# 20_FPGA_Power.net
KiCad netlist of a schematic drawn in Altium Designer
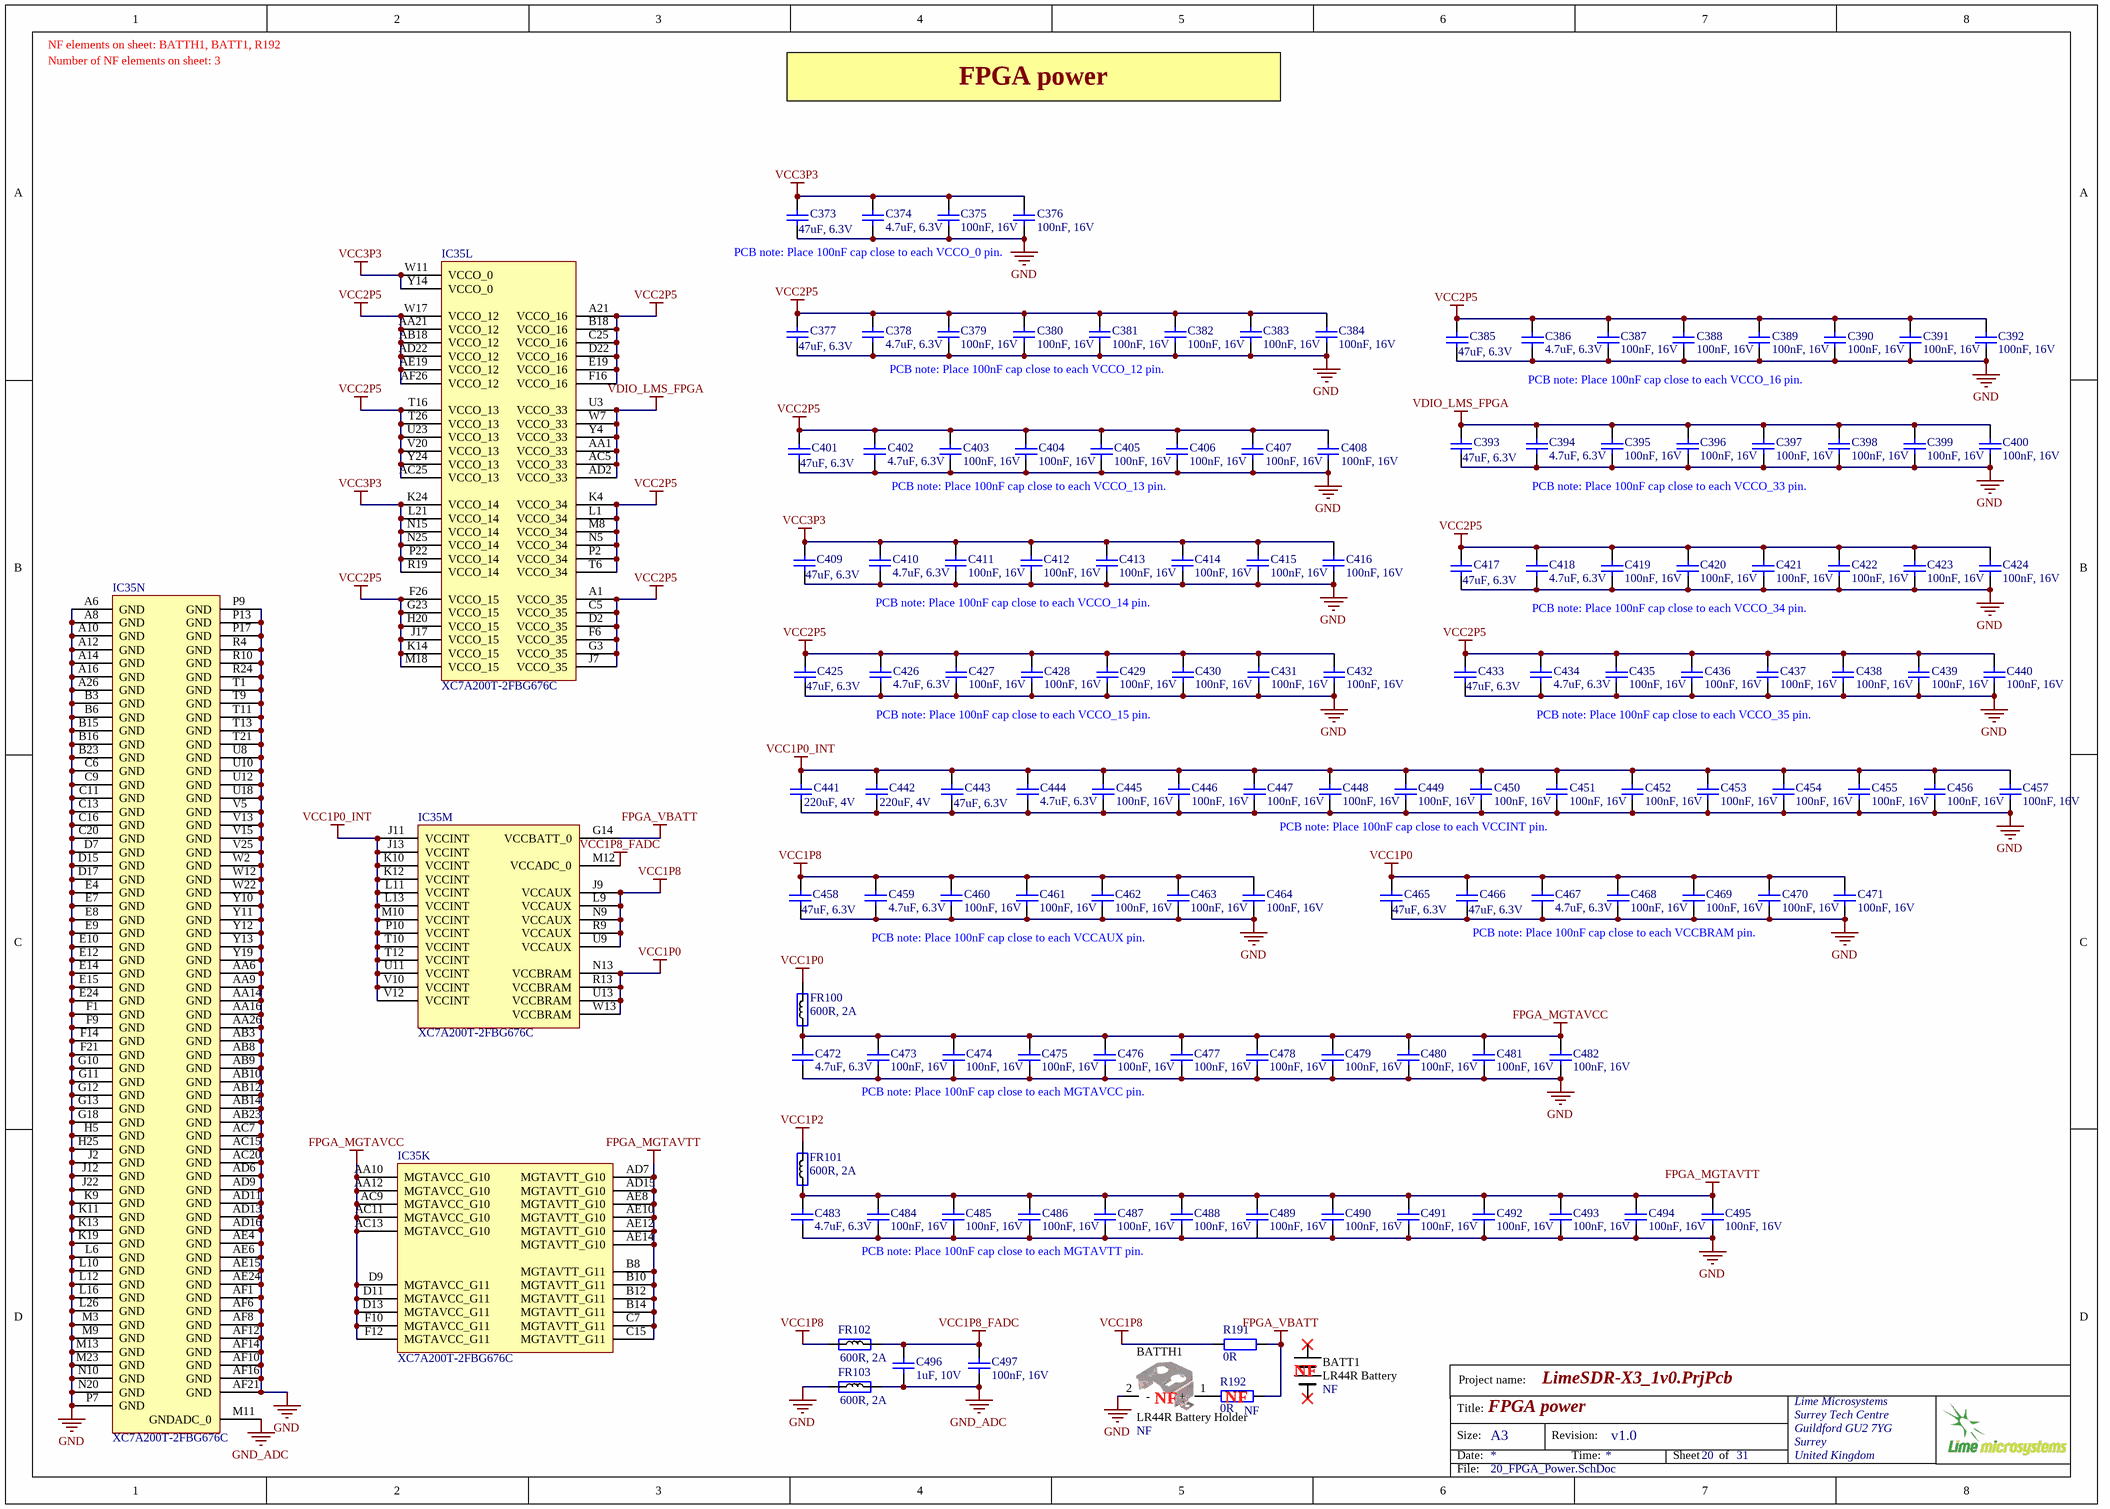
[diagram p0: 20_FPGA_Power.SchDoc]

(export (version "E")
  (design (tool "Eeschema 10.0.6"))
  (components
    (comp (ref "BATT1")
      (value "LR44R Battery")
      (fields (field (name "MANUFACTURER") "Murata") (field (name "ASSEMBLY INFO") "NF"))
      (libsource (lib "LimeMicroAltiumLib_schLib_r03") (part "LR44R_BATTERY"))
    )
    (comp (ref "BATTH1")
      (value "LR44R Battery Holder")
      (footprint "LR44R_BATTERY_HOLDER")
      (fields (field (name "MANUFACTURER") "Keystone Electronics") (field (name "ASSEMBLY INFO") "NF"))
      (libsource (lib "LimeMicroAltiumLib_schLib_r04") (part "LR44R_BATTERY_HOLDER"))
    )
    (comp (ref "C373")
      (value "47uF, 6.3V")
      (footprint "CAP1206")
      (fields
        (field (name "TOLERANCE") "±20%")
        (field (name "MANUFACTURER") "Samsung Electro-Mechanics")
        (field (name "MANUFACTURER PART NUMBER") "CL31A476MQHNNNE")
      )
      (libsource (lib "") (part "Cap_1206_2"))
    )
    (comp (ref "C374")
      (value "4.7uF, 6.3V")
      (footprint "CAP0402")
      (fields
        (field (name "MANUFACTURER") "Murata Electronics North America")
        (field (name "TOLERANCE") "±20%")
      )
      (libsource (lib "LimeMicroAltiumLib_schLib") (part "Cap_0402"))
    )
    (comp (ref "C375")
      (value "100nF, 16V")
      (footprint "CAP0402")
      (fields (field (name "MANUFACTURER") "Murata Electronics") (field (name "TOLERANCE") "10 %"))
      (libsource (lib "LimeMicroAltiumLib_schLib") (part "Cap_0402"))
    )
    (comp (ref "C376")
      (value "100nF, 16V")
      (footprint "CAP0402")
      (fields (field (name "MANUFACTURER") "Murata Electronics") (field (name "TOLERANCE") "10 %"))
      (libsource (lib "LimeMicroAltiumLib_schLib") (part "Cap_0402"))
    )
    (comp (ref "C377")
      (value "47uF, 6.3V")
      (footprint "CAP1206")
      (fields
        (field (name "TOLERANCE") "±20%")
        (field (name "MANUFACTURER") "Samsung Electro-Mechanics")
        (field (name "MANUFACTURER PART NUMBER") "CL31A476MQHNNNE")
      )
      (libsource (lib "") (part "Cap_1206_2"))
    )
    (comp (ref "C378")
      (value "4.7uF, 6.3V")
      (footprint "CAP0402")
      (fields
        (field (name "MANUFACTURER") "Murata Electronics North America")
        (field (name "TOLERANCE") "±20%")
      )
      (libsource (lib "LimeMicroAltiumLib_schLib") (part "Cap_0402"))
    )
    (comp (ref "C379")
      (value "100nF, 16V")
      (footprint "CAP0402")
      (fields (field (name "MANUFACTURER") "Murata Electronics") (field (name "TOLERANCE") "10 %"))
      (libsource (lib "LimeMicroAltiumLib_schLib") (part "Cap_0402"))
    )
    (comp (ref "C380")
      (value "100nF, 16V")
      (footprint "CAP0402")
      (fields (field (name "MANUFACTURER") "Murata Electronics") (field (name "TOLERANCE") "10 %"))
      (libsource (lib "LimeMicroAltiumLib_schLib") (part "Cap_0402"))
    )
    (comp (ref "C381")
      (value "100nF, 16V")
      (footprint "CAP0402")
      (fields (field (name "MANUFACTURER") "Murata Electronics") (field (name "TOLERANCE") "10 %"))
      (libsource (lib "") (part "Cap_0402_1"))
    )
    (comp (ref "C382")
      (value "100nF, 16V")
      (footprint "CAP0402")
      (fields (field (name "MANUFACTURER") "Murata Electronics") (field (name "TOLERANCE") "10 %"))
      (libsource (lib "") (part "Cap_0402_2"))
    )
    (comp (ref "C383")
      (value "100nF, 16V")
      (footprint "CAP0402")
      (fields (field (name "MANUFACTURER") "Murata Electronics") (field (name "TOLERANCE") "10 %"))
      (libsource (lib "") (part "Cap_0402_2"))
    )
    (comp (ref "C384")
      (value "100nF, 16V")
      (footprint "CAP0402")
      (fields (field (name "MANUFACTURER") "Murata Electronics") (field (name "TOLERANCE") "10 %"))
      (libsource (lib "LimeMicroAltiumLib_schLib") (part "Cap_0402"))
    )
    (comp (ref "C385")
      (value "47uF, 6.3V")
      (footprint "CAP1206")
      (fields
        (field (name "TOLERANCE") "±20%")
        (field (name "MANUFACTURER") "Samsung Electro-Mechanics")
        (field (name "MANUFACTURER PART NUMBER") "CL31A476MQHNNNE")
      )
      (libsource (lib "") (part "Cap_1206_2"))
    )
    (comp (ref "C386")
      (value "4.7uF, 6.3V")
      (footprint "CAP0402")
      (fields
        (field (name "MANUFACTURER") "Murata Electronics North America")
        (field (name "TOLERANCE") "±20%")
      )
      (libsource (lib "LimeMicroAltiumLib_schLib") (part "Cap_0402"))
    )
    (comp (ref "C387")
      (value "100nF, 16V")
      (footprint "CAP0402")
      (fields (field (name "MANUFACTURER") "Murata Electronics") (field (name "TOLERANCE") "10 %"))
      (libsource (lib "LimeMicroAltiumLib_schLib") (part "Cap_0402"))
    )
    (comp (ref "C388")
      (value "100nF, 16V")
      (footprint "CAP0402")
      (fields (field (name "MANUFACTURER") "Murata Electronics") (field (name "TOLERANCE") "10 %"))
      (libsource (lib "LimeMicroAltiumLib_schLib") (part "Cap_0402"))
    )
    (comp (ref "C389")
      (value "100nF, 16V")
      (footprint "CAP0402")
      (fields (field (name "MANUFACTURER") "Murata Electronics") (field (name "TOLERANCE") "10 %"))
      (libsource (lib "") (part "Cap_0402_1"))
    )
    (comp (ref "C390")
      (value "100nF, 16V")
      (footprint "CAP0402")
      (fields (field (name "MANUFACTURER") "Murata Electronics") (field (name "TOLERANCE") "10 %"))
      (libsource (lib "") (part "Cap_0402_2"))
    )
    (comp (ref "C391")
      (value "100nF, 16V")
      (footprint "CAP0402")
      (fields (field (name "MANUFACTURER") "Murata Electronics") (field (name "TOLERANCE") "10 %"))
      (libsource (lib "") (part "Cap_0402_2"))
    )
    (comp (ref "C392")
      (value "100nF, 16V")
      (footprint "CAP0402")
      (fields (field (name "MANUFACTURER") "Murata Electronics") (field (name "TOLERANCE") "10 %"))
      (libsource (lib "LimeMicroAltiumLib_schLib") (part "Cap_0402"))
    )
    (comp (ref "C393")
      (value "47uF, 6.3V")
      (footprint "CAP1206")
      (fields
        (field (name "TOLERANCE") "±20%")
        (field (name "MANUFACTURER") "Samsung Electro-Mechanics")
        (field (name "MANUFACTURER PART NUMBER") "CL31A476MQHNNNE")
      )
      (libsource (lib "LimeFPGAboard_schLib") (part "Cap_1206"))
    )
    (comp (ref "C394")
      (value "4.7uF, 6.3V")
      (footprint "CAP0402")
      (fields
        (field (name "MANUFACTURER") "Murata Electronics North America")
        (field (name "TOLERANCE") "±20%")
      )
      (libsource (lib "LimeMicroAltiumLib_schLib") (part "Cap_0402"))
    )
    (comp (ref "C395")
      (value "100nF, 16V")
      (footprint "CAP0402")
      (fields (field (name "MANUFACTURER") "Murata Electronics") (field (name "TOLERANCE") "10 %"))
      (libsource (lib "") (part "Cap_0402_2"))
    )
    (comp (ref "C396")
      (value "100nF, 16V")
      (footprint "CAP0402")
      (fields (field (name "MANUFACTURER") "Murata Electronics") (field (name "TOLERANCE") "10 %"))
      (libsource (lib "LimeMicroAltiumLib_schLib") (part "Cap_0402"))
    )
    (comp (ref "C397")
      (value "100nF, 16V")
      (footprint "CAP0402")
      (fields (field (name "MANUFACTURER") "Murata Electronics") (field (name "TOLERANCE") "10 %"))
      (libsource (lib "LimeMicroAltiumLib_schLib") (part "Cap_0402"))
    )
    (comp (ref "C398")
      (value "100nF, 16V")
      (footprint "CAP0402")
      (fields (field (name "MANUFACTURER") "Murata Electronics") (field (name "TOLERANCE") "10 %"))
      (libsource (lib "") (part "Cap_0402_1"))
    )
    (comp (ref "C399")
      (value "100nF, 16V")
      (footprint "CAP0402")
      (fields (field (name "MANUFACTURER") "Murata Electronics") (field (name "TOLERANCE") "10 %"))
      (libsource (lib "") (part "Cap_0402_2"))
    )
    (comp (ref "C400")
      (value "100nF, 16V")
      (footprint "CAP0402")
      (fields (field (name "MANUFACTURER") "Murata Electronics") (field (name "TOLERANCE") "10 %"))
      (libsource (lib "") (part "Cap_0402_2"))
    )
    (comp (ref "C401")
      (value "47uF, 6.3V")
      (footprint "CAP1206")
      (fields
        (field (name "TOLERANCE") "±20%")
        (field (name "MANUFACTURER") "Samsung Electro-Mechanics")
        (field (name "MANUFACTURER PART NUMBER") "CL31A476MQHNNNE")
      )
      (libsource (lib "") (part "Cap_1206_1"))
    )
    (comp (ref "C402")
      (value "4.7uF, 6.3V")
      (footprint "CAP0402")
      (fields
        (field (name "MANUFACTURER") "Murata Electronics North America")
        (field (name "TOLERANCE") "±20%")
      )
      (libsource (lib "") (part "Cap_0402_2"))
    )
    (comp (ref "C403")
      (value "100nF, 16V")
      (footprint "CAP0402")
      (fields (field (name "MANUFACTURER") "Murata Electronics") (field (name "TOLERANCE") "10 %"))
      (libsource (lib "") (part "Cap_0402_1"))
    )
    (comp (ref "C404")
      (value "100nF, 16V")
      (footprint "CAP0402")
      (fields (field (name "MANUFACTURER") "Murata Electronics") (field (name "TOLERANCE") "10 %"))
      (libsource (lib "") (part "Cap_0402_2"))
    )
    (comp (ref "C405")
      (value "100nF, 16V")
      (footprint "CAP0402")
      (fields (field (name "MANUFACTURER") "Murata Electronics") (field (name "TOLERANCE") "10 %"))
      (libsource (lib "") (part "Cap_0402_2"))
    )
    (comp (ref "C406")
      (value "100nF, 16V")
      (footprint "CAP0402")
      (fields (field (name "MANUFACTURER") "Murata Electronics") (field (name "TOLERANCE") "10 %"))
      (libsource (lib "LimeMicroAltiumLib_schLib") (part "Cap_0402"))
    )
    (comp (ref "C407")
      (value "100nF, 16V")
      (footprint "CAP0402")
      (fields (field (name "MANUFACTURER") "Murata Electronics") (field (name "TOLERANCE") "10 %"))
      (libsource (lib "LimeMicroAltiumLib_schLib") (part "Cap_0402"))
    )
    (comp (ref "C408")
      (value "100nF, 16V")
      (footprint "CAP0402")
      (fields (field (name "MANUFACTURER") "Murata Electronics") (field (name "TOLERANCE") "10 %"))
      (libsource (lib "") (part "Cap_0402_1"))
    )
    (comp (ref "C409")
      (value "47uF, 6.3V")
      (footprint "CAP1206")
      (fields
        (field (name "TOLERANCE") "±20%")
        (field (name "MANUFACTURER") "Samsung Electro-Mechanics")
        (field (name "MANUFACTURER PART NUMBER") "CL31A476MQHNNNE")
      )
      (libsource (lib "") (part "Cap_1206_1"))
    )
    (comp (ref "C410")
      (value "4.7uF, 6.3V")
      (footprint "CAP0402")
      (fields
        (field (name "MANUFACTURER") "Murata Electronics North America")
        (field (name "TOLERANCE") "±20%")
      )
      (libsource (lib "") (part "Cap_0402_2"))
    )
    (comp (ref "C411")
      (value "100nF, 16V")
      (footprint "CAP0402")
      (fields (field (name "MANUFACTURER") "Murata Electronics") (field (name "TOLERANCE") "10 %"))
      (libsource (lib "") (part "Cap_0402_1"))
    )
    (comp (ref "C412")
      (value "100nF, 16V")
      (footprint "CAP0402")
      (fields (field (name "MANUFACTURER") "Murata Electronics") (field (name "TOLERANCE") "10 %"))
      (libsource (lib "") (part "Cap_0402_2"))
    )
    (comp (ref "C413")
      (value "100nF, 16V")
      (footprint "CAP0402")
      (fields (field (name "MANUFACTURER") "Murata Electronics") (field (name "TOLERANCE") "10 %"))
      (libsource (lib "") (part "Cap_0402_2"))
    )
    (comp (ref "C414")
      (value "100nF, 16V")
      (footprint "CAP0402")
      (fields (field (name "MANUFACTURER") "Murata Electronics") (field (name "TOLERANCE") "10 %"))
      (libsource (lib "LimeMicroAltiumLib_schLib") (part "Cap_0402"))
    )
    (comp (ref "C415")
      (value "100nF, 16V")
      (footprint "CAP0402")
      (fields (field (name "MANUFACTURER") "Murata Electronics") (field (name "TOLERANCE") "10 %"))
      (libsource (lib "LimeMicroAltiumLib_schLib") (part "Cap_0402"))
    )
    (comp (ref "C416")
      (value "100nF, 16V")
      (footprint "CAP0402")
      (fields (field (name "MANUFACTURER") "Murata Electronics") (field (name "TOLERANCE") "10 %"))
      (libsource (lib "") (part "Cap_0402_1"))
    )
    (comp (ref "C417")
      (value "47uF, 6.3V")
      (footprint "CAP1206")
      (fields
        (field (name "TOLERANCE") "±20%")
        (field (name "MANUFACTURER") "Samsung Electro-Mechanics")
        (field (name "MANUFACTURER PART NUMBER") "CL31A476MQHNNNE")
      )
      (libsource (lib "LimeFPGAboard_schLib") (part "Cap_1206"))
    )
    (comp (ref "C418")
      (value "4.7uF, 6.3V")
      (footprint "CAP0402")
      (fields
        (field (name "MANUFACTURER") "Murata Electronics North America")
        (field (name "TOLERANCE") "±20%")
      )
      (libsource (lib "LimeMicroAltiumLib_schLib") (part "Cap_0402"))
    )
    (comp (ref "C419")
      (value "100nF, 16V")
      (footprint "CAP0402")
      (fields (field (name "MANUFACTURER") "Murata Electronics") (field (name "TOLERANCE") "10 %"))
      (libsource (lib "") (part "Cap_0402_2"))
    )
    (comp (ref "C420")
      (value "100nF, 16V")
      (footprint "CAP0402")
      (fields (field (name "MANUFACTURER") "Murata Electronics") (field (name "TOLERANCE") "10 %"))
      (libsource (lib "LimeMicroAltiumLib_schLib") (part "Cap_0402"))
    )
    (comp (ref "C421")
      (value "100nF, 16V")
      (footprint "CAP0402")
      (fields (field (name "MANUFACTURER") "Murata Electronics") (field (name "TOLERANCE") "10 %"))
      (libsource (lib "LimeMicroAltiumLib_schLib") (part "Cap_0402"))
    )
    (comp (ref "C422")
      (value "100nF, 16V")
      (footprint "CAP0402")
      (fields (field (name "MANUFACTURER") "Murata Electronics") (field (name "TOLERANCE") "10 %"))
      (libsource (lib "") (part "Cap_0402_1"))
    )
    (comp (ref "C423")
      (value "100nF, 16V")
      (footprint "CAP0402")
      (fields (field (name "MANUFACTURER") "Murata Electronics") (field (name "TOLERANCE") "10 %"))
      (libsource (lib "") (part "Cap_0402_2"))
    )
    (comp (ref "C424")
      (value "100nF, 16V")
      (footprint "CAP0402")
      (fields (field (name "MANUFACTURER") "Murata Electronics") (field (name "TOLERANCE") "10 %"))
      (libsource (lib "") (part "Cap_0402_2"))
    )
    (comp (ref "C425")
      (value "47uF, 6.3V")
      (footprint "CAP1206")
      (fields
        (field (name "TOLERANCE") "±20%")
        (field (name "MANUFACTURER") "Samsung Electro-Mechanics")
        (field (name "MANUFACTURER PART NUMBER") "CL31A476MQHNNNE")
      )
      (libsource (lib "") (part "Cap_1206_1"))
    )
    (comp (ref "C426")
      (value "4.7uF, 6.3V")
      (footprint "CAP0402")
      (fields
        (field (name "MANUFACTURER") "Murata Electronics North America")
        (field (name "TOLERANCE") "±20%")
      )
      (libsource (lib "") (part "Cap_0402_2"))
    )
    (comp (ref "C427")
      (value "100nF, 16V")
      (footprint "CAP0402")
      (fields (field (name "MANUFACTURER") "Murata Electronics") (field (name "TOLERANCE") "10 %"))
      (libsource (lib "") (part "Cap_0402_1"))
    )
    (comp (ref "C428")
      (value "100nF, 16V")
      (footprint "CAP0402")
      (fields (field (name "MANUFACTURER") "Murata Electronics") (field (name "TOLERANCE") "10 %"))
      (libsource (lib "") (part "Cap_0402_2"))
    )
    (comp (ref "C429")
      (value "100nF, 16V")
      (footprint "CAP0402")
      (fields (field (name "MANUFACTURER") "Murata Electronics") (field (name "TOLERANCE") "10 %"))
      (libsource (lib "") (part "Cap_0402_2"))
    )
    (comp (ref "C430")
      (value "100nF, 16V")
      (footprint "CAP0402")
      (fields (field (name "MANUFACTURER") "Murata Electronics") (field (name "TOLERANCE") "10 %"))
      (libsource (lib "LimeMicroAltiumLib_schLib") (part "Cap_0402"))
    )
    (comp (ref "C431")
      (value "100nF, 16V")
      (footprint "CAP0402")
      (fields (field (name "MANUFACTURER") "Murata Electronics") (field (name "TOLERANCE") "10 %"))
      (libsource (lib "LimeMicroAltiumLib_schLib") (part "Cap_0402"))
    )
    (comp (ref "C432")
      (value "100nF, 16V")
      (footprint "CAP0402")
      (fields (field (name "MANUFACTURER") "Murata Electronics") (field (name "TOLERANCE") "10 %"))
      (libsource (lib "") (part "Cap_0402_1"))
    )
    (comp (ref "C433")
      (value "47uF, 6.3V")
      (footprint "CAP1206")
      (fields
        (field (name "TOLERANCE") "±20%")
        (field (name "MANUFACTURER") "Samsung Electro-Mechanics")
        (field (name "MANUFACTURER PART NUMBER") "CL31A476MQHNNNE")
      )
      (libsource (lib "") (part "Cap_1206_1"))
    )
    (comp (ref "C434")
      (value "4.7uF, 6.3V")
      (footprint "CAP0402")
      (fields
        (field (name "MANUFACTURER") "Murata Electronics North America")
        (field (name "TOLERANCE") "±20%")
      )
      (libsource (lib "") (part "Cap_0402_1"))
    )
    (comp (ref "C435")
      (value "100nF, 16V")
      (footprint "CAP0402")
      (fields (field (name "MANUFACTURER") "Murata Electronics") (field (name "TOLERANCE") "10 %"))
      (libsource (lib "") (part "Cap_0402_2"))
    )
    (comp (ref "C436")
      (value "100nF, 16V")
      (footprint "CAP0402")
      (fields (field (name "MANUFACTURER") "Murata Electronics") (field (name "TOLERANCE") "10 %"))
      (libsource (lib "") (part "Cap_0402_2"))
    )
    (comp (ref "C437")
      (value "100nF, 16V")
      (footprint "CAP0402")
      (fields (field (name "MANUFACTURER") "Murata Electronics") (field (name "TOLERANCE") "10 %"))
      (libsource (lib "LimeMicroAltiumLib_schLib") (part "Cap_0402"))
    )
    (comp (ref "C438")
      (value "100nF, 16V")
      (footprint "CAP0402")
      (fields (field (name "MANUFACTURER") "Murata Electronics") (field (name "TOLERANCE") "10 %"))
      (libsource (lib "LimeMicroAltiumLib_schLib") (part "Cap_0402"))
    )
    (comp (ref "C439")
      (value "100nF, 16V")
      (footprint "CAP0402")
      (fields (field (name "MANUFACTURER") "Murata Electronics") (field (name "TOLERANCE") "10 %"))
      (libsource (lib "") (part "Cap_0402_1"))
    )
    (comp (ref "C440")
      (value "100nF, 16V")
      (footprint "CAP0402")
      (fields (field (name "MANUFACTURER") "Murata Electronics") (field (name "TOLERANCE") "10 %"))
      (libsource (lib "") (part "Cap_0402_2"))
    )
    (comp (ref "C441")
      (value "220uF, 4V")
      (footprint "CAP1206")
      (fields
        (field (name "MANUFACTURER") "Murata Electronics North America")
        (field (name "TOLERANCE") "±20%")
      )
      (libsource (lib "LimeFPGAboard_schLib") (part "Cap_1206"))
    )
    (comp (ref "C442")
      (value "220uF, 4V")
      (footprint "CAP1206")
      (fields
        (field (name "MANUFACTURER") "Murata Electronics North America")
        (field (name "TOLERANCE") "±20%")
      )
      (libsource (lib "") (part "Cap_1206_2"))
    )
    (comp (ref "C443")
      (value "47uF, 6.3V")
      (footprint "CAP1206")
      (fields
        (field (name "TOLERANCE") "±20%")
        (field (name "MANUFACTURER") "Samsung Electro-Mechanics")
        (field (name "MANUFACTURER PART NUMBER") "CL31A476MQHNNNE")
      )
      (libsource (lib "") (part "Cap_1206_2"))
    )
    (comp (ref "C444")
      (value "4.7uF, 6.3V")
      (footprint "CAP0402")
      (fields
        (field (name "MANUFACTURER") "Murata Electronics North America")
        (field (name "TOLERANCE") "±20%")
      )
      (libsource (lib "") (part "Cap_0402_2"))
    )
    (comp (ref "C445")
      (value "100nF, 16V")
      (footprint "CAP0402")
      (fields (field (name "MANUFACTURER") "Murata Electronics") (field (name "TOLERANCE") "10 %"))
      (libsource (lib "LimeMicroAltiumLib_schLib") (part "Cap_0402"))
    )
    (comp (ref "C446")
      (value "100nF, 16V")
      (footprint "CAP0402")
      (fields (field (name "MANUFACTURER") "Murata Electronics") (field (name "TOLERANCE") "10 %"))
      (libsource (lib "") (part "Cap_0402_1"))
    )
    (comp (ref "C447")
      (value "100nF, 16V")
      (footprint "CAP0402")
      (fields (field (name "MANUFACTURER") "Murata Electronics") (field (name "TOLERANCE") "10 %"))
      (libsource (lib "") (part "Cap_0402_2"))
    )
    (comp (ref "C448")
      (value "100nF, 16V")
      (footprint "CAP0402")
      (fields (field (name "MANUFACTURER") "Murata Electronics") (field (name "TOLERANCE") "10 %"))
      (libsource (lib "") (part "Cap_0402_2"))
    )
    (comp (ref "C449")
      (value "100nF, 16V")
      (footprint "CAP0402")
      (fields (field (name "MANUFACTURER") "Murata Electronics") (field (name "TOLERANCE") "10 %"))
      (libsource (lib "LimeMicroAltiumLib_schLib") (part "Cap_0402"))
    )
    (comp (ref "C450")
      (value "100nF, 16V")
      (footprint "CAP0402")
      (fields (field (name "MANUFACTURER") "Murata Electronics") (field (name "TOLERANCE") "10 %"))
      (libsource (lib "LimeMicroAltiumLib_schLib") (part "Cap_0402"))
    )
    (comp (ref "C451")
      (value "100nF, 16V")
      (footprint "CAP0402")
      (fields (field (name "MANUFACTURER") "Murata Electronics") (field (name "TOLERANCE") "10 %"))
      (libsource (lib "") (part "Cap_0402_1"))
    )
    (comp (ref "C452")
      (value "100nF, 16V")
      (footprint "CAP0402")
      (fields (field (name "MANUFACTURER") "Murata Electronics") (field (name "TOLERANCE") "10 %"))
      (libsource (lib "") (part "Cap_0402_2"))
    )
    (comp (ref "C453")
      (value "100nF, 16V")
      (footprint "CAP0402")
      (fields (field (name "MANUFACTURER") "Murata Electronics") (field (name "TOLERANCE") "10 %"))
      (libsource (lib "") (part "Cap_0402_2"))
    )
    (comp (ref "C454")
      (value "100nF, 16V")
      (footprint "CAP0402")
      (fields (field (name "MANUFACTURER") "Murata Electronics") (field (name "TOLERANCE") "10 %"))
      (libsource (lib "LimeMicroAltiumLib_schLib") (part "Cap_0402"))
    )
    (comp (ref "C455")
      (value "100nF, 16V")
      (footprint "CAP0402")
      (fields (field (name "MANUFACTURER") "Murata Electronics") (field (name "TOLERANCE") "10 %"))
      (libsource (lib "LimeMicroAltiumLib_schLib") (part "Cap_0402"))
    )
    (comp (ref "C456")
      (value "100nF, 16V")
      (footprint "CAP0402")
      (fields (field (name "MANUFACTURER") "Murata Electronics") (field (name "TOLERANCE") "10 %"))
      (libsource (lib "") (part "Cap_0402_1"))
    )
    (comp (ref "C457")
      (value "100nF, 16V")
      (footprint "CAP0402")
      (fields (field (name "MANUFACTURER") "Murata Electronics") (field (name "TOLERANCE") "10 %"))
      (libsource (lib "") (part "Cap_0402_2"))
    )
    (comp (ref "C458")
      (value "47uF, 6.3V")
      (footprint "CAP1206")
      (fields
        (field (name "TOLERANCE") "±20%")
        (field (name "MANUFACTURER") "Samsung Electro-Mechanics")
        (field (name "MANUFACTURER PART NUMBER") "CL31A476MQHNNNE")
      )
      (libsource (lib "") (part "Cap_1206_1"))
    )
    (comp (ref "C459")
      (value "4.7uF, 6.3V")
      (footprint "CAP0402")
      (fields
        (field (name "MANUFACTURER") "Murata Electronics North America")
        (field (name "TOLERANCE") "±20%")
      )
      (libsource (lib "") (part "Cap_0402_2"))
    )
    (comp (ref "C460")
      (value "100nF, 16V")
      (footprint "CAP0402")
      (fields (field (name "MANUFACTURER") "Murata Electronics") (field (name "TOLERANCE") "10 %"))
      (libsource (lib "") (part "Cap_0402_1"))
    )
    (comp (ref "C461")
      (value "100nF, 16V")
      (footprint "CAP0402")
      (fields (field (name "MANUFACTURER") "Murata Electronics") (field (name "TOLERANCE") "10 %"))
      (libsource (lib "") (part "Cap_0402_2"))
    )
    (comp (ref "C462")
      (value "100nF, 16V")
      (footprint "CAP0402")
      (fields (field (name "MANUFACTURER") "Murata Electronics") (field (name "TOLERANCE") "10 %"))
      (libsource (lib "") (part "Cap_0402_2"))
    )
    (comp (ref "C463")
      (value "100nF, 16V")
      (footprint "CAP0402")
      (fields (field (name "MANUFACTURER") "Murata Electronics") (field (name "TOLERANCE") "10 %"))
      (libsource (lib "LimeMicroAltiumLib_schLib") (part "Cap_0402"))
    )
    (comp (ref "C464")
      (value "100nF, 16V")
      (footprint "CAP0402")
      (fields (field (name "MANUFACTURER") "Murata Electronics") (field (name "TOLERANCE") "10 %"))
      (libsource (lib "LimeMicroAltiumLib_schLib") (part "Cap_0402"))
    )
    (comp (ref "C465")
      (value "47uF, 6.3V")
      (footprint "CAP1206")
      (fields
        (field (name "TOLERANCE") "±20%")
        (field (name "MANUFACTURER") "Samsung Electro-Mechanics")
        (field (name "MANUFACTURER PART NUMBER") "CL31A476MQHNNNE")
      )
      (libsource (lib "") (part "Cap_1206_1"))
    )
    (comp (ref "C466")
      (value "47uF, 6.3V")
      (footprint "CAP1206")
      (fields
        (field (name "TOLERANCE") "±20%")
        (field (name "MANUFACTURER") "Samsung Electro-Mechanics")
        (field (name "MANUFACTURER PART NUMBER") "CL31A476MQHNNNE")
      )
      (libsource (lib "LimeFPGAboard_schLib") (part "Cap_1206"))
    )
    (comp (ref "C467")
      (value "4.7uF, 6.3V")
      (footprint "CAP0402")
      (fields
        (field (name "MANUFACTURER") "Murata Electronics North America")
        (field (name "TOLERANCE") "±20%")
      )
      (libsource (lib "LimeMicroAltiumLib_schLib") (part "Cap_0402"))
    )
    (comp (ref "C468")
      (value "100nF, 16V")
      (footprint "CAP0402")
      (fields (field (name "MANUFACTURER") "Murata Electronics") (field (name "TOLERANCE") "10 %"))
      (libsource (lib "") (part "Cap_0402_2"))
    )
    (comp (ref "C469")
      (value "100nF, 16V")
      (footprint "CAP0402")
      (fields (field (name "MANUFACTURER") "Murata Electronics") (field (name "TOLERANCE") "10 %"))
      (libsource (lib "LimeMicroAltiumLib_schLib") (part "Cap_0402"))
    )
    (comp (ref "C470")
      (value "100nF, 16V")
      (footprint "CAP0402")
      (fields (field (name "MANUFACTURER") "Murata Electronics") (field (name "TOLERANCE") "10 %"))
      (libsource (lib "LimeMicroAltiumLib_schLib") (part "Cap_0402"))
    )
    (comp (ref "C471")
      (value "100nF, 16V")
      (footprint "CAP0402")
      (fields (field (name "MANUFACTURER") "Murata Electronics") (field (name "TOLERANCE") "10 %"))
      (libsource (lib "LimeMicroAltiumLib_schLib") (part "Cap_0402"))
    )
    (comp (ref "C472")
      (value "4.7uF, 6.3V")
      (footprint "CAP0402")
      (fields
        (field (name "MANUFACTURER") "Murata Electronics North America")
        (field (name "TOLERANCE") "±20%")
      )
      (libsource (lib "") (part "Cap_0402_1"))
    )
    (comp (ref "C473")
      (value "100nF, 16V")
      (footprint "CAP0402")
      (fields (field (name "MANUFACTURER") "Murata Electronics") (field (name "TOLERANCE") "10 %"))
      (libsource (lib "") (part "Cap_0402_2"))
    )
    (comp (ref "C474")
      (value "100nF, 16V")
      (footprint "CAP0402")
      (fields (field (name "MANUFACTURER") "Murata Electronics") (field (name "TOLERANCE") "10 %"))
      (libsource (lib "") (part "Cap_0402_2"))
    )
    (comp (ref "C475")
      (value "100nF, 16V")
      (footprint "CAP0402")
      (fields (field (name "MANUFACTURER") "Murata Electronics") (field (name "TOLERANCE") "10 %"))
      (libsource (lib "LimeMicroAltiumLib_schLib") (part "Cap_0402"))
    )
    (comp (ref "C476")
      (value "100nF, 16V")
      (footprint "CAP0402")
      (fields (field (name "MANUFACTURER") "Murata Electronics") (field (name "TOLERANCE") "10 %"))
      (libsource (lib "LimeMicroAltiumLib_schLib") (part "Cap_0402"))
    )
    (comp (ref "C477")
      (value "100nF, 16V")
      (footprint "CAP0402")
      (fields (field (name "MANUFACTURER") "Murata Electronics") (field (name "TOLERANCE") "10 %"))
      (libsource (lib "") (part "Cap_0402_3"))
    )
    (comp (ref "C478")
      (value "100nF, 16V")
      (footprint "CAP0402")
      (fields (field (name "MANUFACTURER") "Murata Electronics") (field (name "TOLERANCE") "10 %"))
      (libsource (lib "") (part "Cap_0402_2"))
    )
    (comp (ref "C479")
      (value "100nF, 16V")
      (footprint "CAP0402")
      (fields (field (name "MANUFACTURER") "Murata Electronics") (field (name "TOLERANCE") "10 %"))
      (libsource (lib "") (part "Cap_0402_2"))
    )
    (comp (ref "C480")
      (value "100nF, 16V")
      (footprint "CAP0402")
      (fields (field (name "MANUFACTURER") "Murata Electronics") (field (name "TOLERANCE") "10 %"))
      (libsource (lib "LimeMicroAltiumLib_schLib") (part "Cap_0402"))
    )
    (comp (ref "C481")
      (value "100nF, 16V")
      (footprint "CAP0402")
      (fields (field (name "MANUFACTURER") "Murata Electronics") (field (name "TOLERANCE") "10 %"))
      (libsource (lib "LimeMicroAltiumLib_schLib") (part "Cap_0402"))
    )
    (comp (ref "C482")
      (value "100nF, 16V")
      (footprint "CAP0402")
      (fields (field (name "MANUFACTURER") "Murata Electronics") (field (name "TOLERANCE") "10 %"))
      (libsource (lib "") (part "Cap_0402_3"))
    )
    (comp (ref "C483")
      (value "4.7uF, 6.3V")
      (footprint "CAP0402")
      (fields
        (field (name "MANUFACTURER") "Murata Electronics North America")
        (field (name "TOLERANCE") "±20%")
      )
      (libsource (lib "") (part "Cap_0402_2"))
    )
    (comp (ref "C484")
      (value "100nF, 16V")
      (footprint "CAP0402")
      (fields (field (name "MANUFACTURER") "Murata Electronics") (field (name "TOLERANCE") "10 %"))
      (libsource (lib "") (part "Cap_0402_2"))
    )
    (comp (ref "C485")
      (value "100nF, 16V")
      (footprint "CAP0402")
      (fields (field (name "MANUFACTURER") "Murata Electronics") (field (name "TOLERANCE") "10 %"))
      (libsource (lib "LimeMicroAltiumLib_schLib") (part "Cap_0402"))
    )
    (comp (ref "C486")
      (value "100nF, 16V")
      (footprint "CAP0402")
      (fields (field (name "MANUFACTURER") "Murata Electronics") (field (name "TOLERANCE") "10 %"))
      (libsource (lib "LimeMicroAltiumLib_schLib") (part "Cap_0402"))
    )
    (comp (ref "C487")
      (value "100nF, 16V")
      (footprint "CAP0402")
      (fields (field (name "MANUFACTURER") "Murata Electronics") (field (name "TOLERANCE") "10 %"))
      (libsource (lib "") (part "Cap_0402_1"))
    )
    (comp (ref "C488")
      (value "100nF, 16V")
      (footprint "CAP0402")
      (fields (field (name "MANUFACTURER") "Murata Electronics") (field (name "TOLERANCE") "10 %"))
      (libsource (lib "") (part "Cap_0402_2"))
    )
    (comp (ref "C489")
      (value "100nF, 16V")
      (footprint "CAP0402")
      (fields (field (name "MANUFACTURER") "Murata Electronics") (field (name "TOLERANCE") "10 %"))
      (libsource (lib "") (part "Cap_0402_2"))
    )
    (comp (ref "C490")
      (value "100nF, 16V")
      (footprint "CAP0402")
      (fields (field (name "MANUFACTURER") "Murata Electronics") (field (name "TOLERANCE") "10 %"))
      (libsource (lib "") (part "Cap_0402_2"))
    )
    (comp (ref "C491")
      (value "100nF, 16V")
      (footprint "CAP0402")
      (fields (field (name "MANUFACTURER") "Murata Electronics") (field (name "TOLERANCE") "10 %"))
      (libsource (lib "LimeMicroAltiumLib_schLib") (part "Cap_0402"))
    )
    (comp (ref "C492")
      (value "100nF, 16V")
      (footprint "CAP0402")
      (fields (field (name "MANUFACTURER") "Murata Electronics") (field (name "TOLERANCE") "10 %"))
      (libsource (lib "LimeMicroAltiumLib_schLib") (part "Cap_0402"))
    )
    (comp (ref "C493")
      (value "100nF, 16V")
      (footprint "CAP0402")
      (fields (field (name "MANUFACTURER") "Murata Electronics") (field (name "TOLERANCE") "10 %"))
      (libsource (lib "") (part "Cap_0402_3"))
    )
    (comp (ref "C494")
      (value "100nF, 16V")
      (footprint "CAP0402")
      (fields (field (name "MANUFACTURER") "Murata Electronics") (field (name "TOLERANCE") "10 %"))
      (libsource (lib "LimeMicroAltiumLib_schLib") (part "Cap_0402"))
    )
    (comp (ref "C495")
      (value "100nF, 16V")
      (footprint "CAP0402")
      (fields (field (name "MANUFACTURER") "Murata Electronics") (field (name "TOLERANCE") "10 %"))
      (libsource (lib "") (part "Cap_0402_3"))
    )
    (comp (ref "C496")
      (value "1uF, 10V")
      (footprint "CAP0402")
      (fields (field (name "MANUFACTURER") "TDK"))
      (libsource (lib "") (part "Cap_0402_1"))
    )
    (comp (ref "C497")
      (value "100nF, 16V")
      (footprint "CAP0402")
      (fields (field (name "MANUFACTURER") "Murata Electronics") (field (name "TOLERANCE") "10 %"))
      (libsource (lib "") (part "Cap_0402_2"))
    )
    (comp (ref "FR100")
      (value "600R, 2A")
      (footprint "RES0805")
      (fields (field (name "MANUFACTURER") "TDK Corporation"))
      (libsource (lib "LimeMicroAltiumLib_schLib") (part "Ferrite"))
    )
    (comp (ref "FR101")
      (value "600R, 2A")
      (footprint "RES0805")
      (fields (field (name "MANUFACTURER") "TDK Corporation"))
      (libsource (lib "LimeMicroAltiumLib_schLib") (part "Ferrite"))
    )
    (comp (ref "FR102")
      (value "600R, 2A")
      (footprint "RES0805")
      (fields (field (name "MANUFACTURER") "TDK Corporation"))
      (libsource (lib "LimeMicroAltiumLib_schLib") (part "Ferrite"))
    )
    (comp (ref "FR103")
      (value "600R, 2A")
      (footprint "RES0805")
      (fields (field (name "MANUFACTURER") "TDK Corporation"))
      (libsource (lib "LimeMicroAltiumLib_schLib") (part "Ferrite"))
    )
    (comp (ref "IC35")
      (value "XC7A200T-2FBG676C")
      (footprint "XC7A200T-2FBG676C_FBG676")
      (description "Artix-7 FPGA, 400 User I/Os, 8 GTP, 676-Ball BGA, Speed Grade 2, Commercial Grade, Pb-Free")
      (fields (field (name "MANUFACTURER") "Xilinx"))
      (libsource (lib "") (part "XC7A200T-2FBG676C_3"))
    )
    (comp (ref "R191")
      (value "0R")
      (footprint "RES0402")
      (fields (field (name "MANUFACTURER") "Yageo") (field (name "TOLERANCE") "Jumper"))
      (libsource (lib "LimeMicroAltiumLib_schLib") (part "Res_0402"))
    )
    (comp (ref "R192")
      (value "0R")
      (footprint "RES0402")
      (fields
        (field (name "ASSEMBLY INFO") "NF")
        (field (name "MANUFACTURER") "Yageo")
        (field (name "TOLERANCE") "Jumper")
      )
      (libsource (lib "LimeMicroAltiumLib_schLib") (part "Res_0402"))
    )
  )
  (nets
    (net (code "1") (name "FPGA_MGTAVCC") (class "Default")
      (node (ref "C472") (pin "2") (pinfunction "2_2") (pintype "passive"))
      (node (ref "C473") (pin "1") (pinfunction "1_1") (pintype "passive"))
      (node (ref "C474") (pin "1") (pinfunction "1_1") (pintype "passive"))
      (node (ref "C475") (pin "1") (pinfunction "1_1") (pintype "passive"))
      (node (ref "C476") (pin "1") (pinfunction "1_1") (pintype "passive"))
      (node (ref "C477") (pin "1") (pinfunction "1_1") (pintype "passive"))
      (node (ref "C478") (pin "1") (pinfunction "1_1") (pintype "passive"))
      (node (ref "C479") (pin "1") (pinfunction "1_1") (pintype "passive"))
      (node (ref "C480") (pin "1") (pinfunction "1_1") (pintype "passive"))
      (node (ref "C481") (pin "1") (pinfunction "1_1") (pintype "passive"))
      (node (ref "C482") (pin "1") (pinfunction "1_1") (pintype "passive"))
      (node (ref "FR100") (pin "1") (pinfunction "1_1") (pintype "passive"))
      (node (ref "IC35") (pin "AA10") (pinfunction "MGTAVCC_G10_AA10") (pintype "power_in"))
      (node (ref "IC35") (pin "AA12") (pinfunction "MGTAVCC_G10_AA12") (pintype "power_in"))
      (node (ref "IC35") (pin "AC11") (pinfunction "MGTAVCC_G10_AC11") (pintype "power_in"))
      (node (ref "IC35") (pin "AC13") (pinfunction "MGTAVCC_G10_AC13") (pintype "power_in"))
      (node (ref "IC35") (pin "AC9") (pinfunction "MGTAVCC_G10_AC9") (pintype "power_in"))
      (node (ref "IC35") (pin "D11") (pinfunction "MGTAVCC_G11_D11") (pintype "power_in"))
      (node (ref "IC35") (pin "D13") (pinfunction "MGTAVCC_G11_D13") (pintype "power_in"))
      (node (ref "IC35") (pin "D9") (pinfunction "MGTAVCC_G11_D9") (pintype "power_in"))
      (node (ref "IC35") (pin "F10") (pinfunction "MGTAVCC_G11_F10") (pintype "power_in"))
      (node (ref "IC35") (pin "F12") (pinfunction "MGTAVCC_G11_F12") (pintype "power_in"))
    )
    (net (code "2") (name "FPGA_MGTAVTT") (class "Default")
      (node (ref "C483") (pin "2") (pinfunction "2_2") (pintype "passive"))
      (node (ref "C484") (pin "1") (pinfunction "1_1") (pintype "passive"))
      (node (ref "C485") (pin "1") (pinfunction "1_1") (pintype "passive"))
      (node (ref "C486") (pin "1") (pinfunction "1_1") (pintype "passive"))
      (node (ref "C487") (pin "1") (pinfunction "1_1") (pintype "passive"))
      (node (ref "C488") (pin "1") (pinfunction "1_1") (pintype "passive"))
      (node (ref "C489") (pin "1") (pinfunction "1_1") (pintype "passive"))
      (node (ref "C490") (pin "1") (pinfunction "1_1") (pintype "passive"))
      (node (ref "C491") (pin "1") (pinfunction "1_1") (pintype "passive"))
      (node (ref "C492") (pin "1") (pinfunction "1_1") (pintype "passive"))
      (node (ref "C493") (pin "1") (pinfunction "1_1") (pintype "passive"))
      (node (ref "C494") (pin "1") (pinfunction "1_1") (pintype "passive"))
      (node (ref "C495") (pin "1") (pinfunction "1_1") (pintype "passive"))
      (node (ref "FR101") (pin "1") (pinfunction "1_1") (pintype "passive"))
      (node (ref "IC35") (pin "AD15") (pinfunction "MGTAVTT_G10_AD15") (pintype "power_in"))
      (node (ref "IC35") (pin "AD7") (pinfunction "MGTAVTT_G10_AD7") (pintype "power_in"))
      (node (ref "IC35") (pin "AE10") (pinfunction "MGTAVTT_G10_AE10") (pintype "power_in"))
      (node (ref "IC35") (pin "AE12") (pinfunction "MGTAVTT_G10_AE12") (pintype "power_in"))
      (node (ref "IC35") (pin "AE14") (pinfunction "MGTAVTT_G10_AE14") (pintype "power_in"))
      (node (ref "IC35") (pin "AE8") (pinfunction "MGTAVTT_G10_AE8") (pintype "power_in"))
      (node (ref "IC35") (pin "B10") (pinfunction "MGTAVTT_G11_B10") (pintype "power_in"))
      (node (ref "IC35") (pin "B12") (pinfunction "MGTAVTT_G11_B12") (pintype "power_in"))
      (node (ref "IC35") (pin "B14") (pinfunction "MGTAVTT_G11_B14") (pintype "power_in"))
      (node (ref "IC35") (pin "B8") (pinfunction "MGTAVTT_G11_B8") (pintype "power_in"))
      (node (ref "IC35") (pin "C15") (pinfunction "MGTAVTT_G11_C15") (pintype "power_in"))
      (node (ref "IC35") (pin "C7") (pinfunction "MGTAVTT_G11_C7") (pintype "power_in"))
    )
    (net (code "3") (name "FPGA_VBATT") (class "Default")
      (node (ref "IC35") (pin "G14") (pinfunction "VCCBATT_0_G14") (pintype "power_in"))
      (node (ref "R191") (pin "2") (pinfunction "2_2") (pintype "passive"))
      (node (ref "R192") (pin "2") (pinfunction "2_2") (pintype "passive"))
    )
    (net (code "4") (name "GND") (class "Default")
      (node (ref "BATTH1") (pin "2") (pinfunction "-_2") (pintype "passive"))
      (node (ref "C373") (pin "1") (pinfunction "1_1") (pintype "passive"))
      (node (ref "C374") (pin "1") (pinfunction "1_1") (pintype "passive"))
      (node (ref "C375") (pin "2") (pinfunction "2_2") (pintype "passive"))
      (node (ref "C376") (pin "2") (pinfunction "2_2") (pintype "passive"))
      (node (ref "C377") (pin "1") (pinfunction "1_1") (pintype "passive"))
      (node (ref "C378") (pin "1") (pinfunction "1_1") (pintype "passive"))
      (node (ref "C379") (pin "2") (pinfunction "2_2") (pintype "passive"))
      (node (ref "C380") (pin "2") (pinfunction "2_2") (pintype "passive"))
      (node (ref "C381") (pin "2") (pinfunction "2_2") (pintype "passive"))
      (node (ref "C382") (pin "2") (pinfunction "2_2") (pintype "passive"))
      (node (ref "C383") (pin "2") (pinfunction "2_2") (pintype "passive"))
      (node (ref "C384") (pin "2") (pinfunction "2_2") (pintype "passive"))
      (node (ref "C385") (pin "1") (pinfunction "1_1") (pintype "passive"))
      (node (ref "C386") (pin "1") (pinfunction "1_1") (pintype "passive"))
      (node (ref "C387") (pin "2") (pinfunction "2_2") (pintype "passive"))
      (node (ref "C388") (pin "2") (pinfunction "2_2") (pintype "passive"))
      (node (ref "C389") (pin "2") (pinfunction "2_2") (pintype "passive"))
      (node (ref "C390") (pin "2") (pinfunction "2_2") (pintype "passive"))
      (node (ref "C391") (pin "2") (pinfunction "2_2") (pintype "passive"))
      (node (ref "C392") (pin "2") (pinfunction "2_2") (pintype "passive"))
      (node (ref "C393") (pin "1") (pinfunction "1_1") (pintype "passive"))
      (node (ref "C394") (pin "1") (pinfunction "1_1") (pintype "passive"))
      (node (ref "C395") (pin "2") (pinfunction "2_2") (pintype "passive"))
      (node (ref "C396") (pin "2") (pinfunction "2_2") (pintype "passive"))
      (node (ref "C397") (pin "2") (pinfunction "2_2") (pintype "passive"))
      (node (ref "C398") (pin "2") (pinfunction "2_2") (pintype "passive"))
      (node (ref "C399") (pin "2") (pinfunction "2_2") (pintype "passive"))
      (node (ref "C400") (pin "2") (pinfunction "2_2") (pintype "passive"))
      (node (ref "C401") (pin "1") (pinfunction "1_1") (pintype "passive"))
      (node (ref "C402") (pin "1") (pinfunction "1_1") (pintype "passive"))
      (node (ref "C403") (pin "2") (pinfunction "2_2") (pintype "passive"))
      (node (ref "C404") (pin "2") (pinfunction "2_2") (pintype "passive"))
      (node (ref "C405") (pin "2") (pinfunction "2_2") (pintype "passive"))
      (node (ref "C406") (pin "2") (pinfunction "2_2") (pintype "passive"))
      (node (ref "C407") (pin "2") (pinfunction "2_2") (pintype "passive"))
      (node (ref "C408") (pin "2") (pinfunction "2_2") (pintype "passive"))
      (node (ref "C409") (pin "1") (pinfunction "1_1") (pintype "passive"))
      (node (ref "C410") (pin "1") (pinfunction "1_1") (pintype "passive"))
      (node (ref "C411") (pin "2") (pinfunction "2_2") (pintype "passive"))
      (node (ref "C412") (pin "2") (pinfunction "2_2") (pintype "passive"))
      (node (ref "C413") (pin "2") (pinfunction "2_2") (pintype "passive"))
      (node (ref "C414") (pin "2") (pinfunction "2_2") (pintype "passive"))
      (node (ref "C415") (pin "2") (pinfunction "2_2") (pintype "passive"))
      (node (ref "C416") (pin "2") (pinfunction "2_2") (pintype "passive"))
      (node (ref "C417") (pin "1") (pinfunction "1_1") (pintype "passive"))
      (node (ref "C418") (pin "1") (pinfunction "1_1") (pintype "passive"))
      (node (ref "C419") (pin "2") (pinfunction "2_2") (pintype "passive"))
      (node (ref "C420") (pin "2") (pinfunction "2_2") (pintype "passive"))
      (node (ref "C421") (pin "2") (pinfunction "2_2") (pintype "passive"))
      (node (ref "C422") (pin "2") (pinfunction "2_2") (pintype "passive"))
      (node (ref "C423") (pin "2") (pinfunction "2_2") (pintype "passive"))
      (node (ref "C424") (pin "2") (pinfunction "2_2") (pintype "passive"))
      (node (ref "C425") (pin "1") (pinfunction "1_1") (pintype "passive"))
      (node (ref "C426") (pin "1") (pinfunction "1_1") (pintype "passive"))
      (node (ref "C427") (pin "2") (pinfunction "2_2") (pintype "passive"))
      (node (ref "C428") (pin "2") (pinfunction "2_2") (pintype "passive"))
      (node (ref "C429") (pin "2") (pinfunction "2_2") (pintype "passive"))
      (node (ref "C430") (pin "2") (pinfunction "2_2") (pintype "passive"))
      (node (ref "C431") (pin "2") (pinfunction "2_2") (pintype "passive"))
      (node (ref "C432") (pin "2") (pinfunction "2_2") (pintype "passive"))
      (node (ref "C433") (pin "1") (pinfunction "1_1") (pintype "passive"))
      (node (ref "C434") (pin "1") (pinfunction "1_1") (pintype "passive"))
      (node (ref "C435") (pin "2") (pinfunction "2_2") (pintype "passive"))
      (node (ref "C436") (pin "2") (pinfunction "2_2") (pintype "passive"))
      (node (ref "C437") (pin "2") (pinfunction "2_2") (pintype "passive"))
      (node (ref "C438") (pin "2") (pinfunction "2_2") (pintype "passive"))
      (node (ref "C439") (pin "2") (pinfunction "2_2") (pintype "passive"))
      (node (ref "C440") (pin "2") (pinfunction "2_2") (pintype "passive"))
      (node (ref "C441") (pin "1") (pinfunction "1_1") (pintype "passive"))
      (node (ref "C442") (pin "1") (pinfunction "1_1") (pintype "passive"))
      (node (ref "C443") (pin "1") (pinfunction "1_1") (pintype "passive"))
      (node (ref "C444") (pin "1") (pinfunction "1_1") (pintype "passive"))
      (node (ref "C445") (pin "2") (pinfunction "2_2") (pintype "passive"))
      (node (ref "C446") (pin "2") (pinfunction "2_2") (pintype "passive"))
      (node (ref "C447") (pin "2") (pinfunction "2_2") (pintype "passive"))
      (node (ref "C448") (pin "2") (pinfunction "2_2") (pintype "passive"))
      (node (ref "C449") (pin "2") (pinfunction "2_2") (pintype "passive"))
      (node (ref "C450") (pin "2") (pinfunction "2_2") (pintype "passive"))
      (node (ref "C451") (pin "2") (pinfunction "2_2") (pintype "passive"))
      (node (ref "C452") (pin "2") (pinfunction "2_2") (pintype "passive"))
      (node (ref "C453") (pin "2") (pinfunction "2_2") (pintype "passive"))
      (node (ref "C454") (pin "2") (pinfunction "2_2") (pintype "passive"))
      (node (ref "C455") (pin "2") (pinfunction "2_2") (pintype "passive"))
      (node (ref "C456") (pin "2") (pinfunction "2_2") (pintype "passive"))
      (node (ref "C457") (pin "2") (pinfunction "2_2") (pintype "passive"))
      (node (ref "C458") (pin "1") (pinfunction "1_1") (pintype "passive"))
      (node (ref "C459") (pin "1") (pinfunction "1_1") (pintype "passive"))
      (node (ref "C460") (pin "2") (pinfunction "2_2") (pintype "passive"))
      (node (ref "C461") (pin "2") (pinfunction "2_2") (pintype "passive"))
      (node (ref "C462") (pin "2") (pinfunction "2_2") (pintype "passive"))
      (node (ref "C463") (pin "2") (pinfunction "2_2") (pintype "passive"))
      (node (ref "C464") (pin "2") (pinfunction "2_2") (pintype "passive"))
      (node (ref "C465") (pin "1") (pinfunction "1_1") (pintype "passive"))
      (node (ref "C466") (pin "1") (pinfunction "1_1") (pintype "passive"))
      (node (ref "C467") (pin "1") (pinfunction "1_1") (pintype "passive"))
      (node (ref "C468") (pin "2") (pinfunction "2_2") (pintype "passive"))
      (node (ref "C469") (pin "2") (pinfunction "2_2") (pintype "passive"))
      (node (ref "C470") (pin "2") (pinfunction "2_2") (pintype "passive"))
      (node (ref "C471") (pin "2") (pinfunction "2_2") (pintype "passive"))
      (node (ref "C472") (pin "1") (pinfunction "1_1") (pintype "passive"))
      (node (ref "C473") (pin "2") (pinfunction "2_2") (pintype "passive"))
      (node (ref "C474") (pin "2") (pinfunction "2_2") (pintype "passive"))
      (node (ref "C475") (pin "2") (pinfunction "2_2") (pintype "passive"))
      (node (ref "C476") (pin "2") (pinfunction "2_2") (pintype "passive"))
      (node (ref "C477") (pin "2") (pinfunction "2_2") (pintype "passive"))
      (node (ref "C478") (pin "2") (pinfunction "2_2") (pintype "passive"))
      (node (ref "C479") (pin "2") (pinfunction "2_2") (pintype "passive"))
      (node (ref "C480") (pin "2") (pinfunction "2_2") (pintype "passive"))
      (node (ref "C481") (pin "2") (pinfunction "2_2") (pintype "passive"))
      (node (ref "C482") (pin "2") (pinfunction "2_2") (pintype "passive"))
      (node (ref "C483") (pin "1") (pinfunction "1_1") (pintype "passive"))
      (node (ref "C484") (pin "2") (pinfunction "2_2") (pintype "passive"))
      (node (ref "C485") (pin "2") (pinfunction "2_2") (pintype "passive"))
      (node (ref "C486") (pin "2") (pinfunction "2_2") (pintype "passive"))
      (node (ref "C487") (pin "2") (pinfunction "2_2") (pintype "passive"))
      (node (ref "C488") (pin "2") (pinfunction "2_2") (pintype "passive"))
      (node (ref "C489") (pin "2") (pinfunction "2_2") (pintype "passive"))
      (node (ref "C490") (pin "2") (pinfunction "2_2") (pintype "passive"))
      (node (ref "C491") (pin "2") (pinfunction "2_2") (pintype "passive"))
      (node (ref "C492") (pin "2") (pinfunction "2_2") (pintype "passive"))
      (node (ref "C493") (pin "2") (pinfunction "2_2") (pintype "passive"))
      (node (ref "C494") (pin "2") (pinfunction "2_2") (pintype "passive"))
      (node (ref "C495") (pin "2") (pinfunction "2_2") (pintype "passive"))
      (node (ref "FR103") (pin "1") (pinfunction "1_1") (pintype "passive"))
      (node (ref "IC35") (pin "A10") (pinfunction "GND_A10") (pintype "power_in"))
      (node (ref "IC35") (pin "A12") (pinfunction "GND_A12") (pintype "power_in"))
      (node (ref "IC35") (pin "A14") (pinfunction "GND_A14") (pintype "power_in"))
      (node (ref "IC35") (pin "A16") (pinfunction "GND_A16") (pintype "power_in"))
      (node (ref "IC35") (pin "A26") (pinfunction "GND_A26") (pintype "power_in"))
      (node (ref "IC35") (pin "A6") (pinfunction "GND_A6") (pintype "power_in"))
      (node (ref "IC35") (pin "A8") (pinfunction "GND_A8") (pintype "power_in"))
      (node (ref "IC35") (pin "AA14") (pinfunction "GND_AA14") (pintype "power_in"))
      (node (ref "IC35") (pin "AA16") (pinfunction "GND_AA16") (pintype "power_in"))
      (node (ref "IC35") (pin "AA26") (pinfunction "GND_AA26") (pintype "power_in"))
      (node (ref "IC35") (pin "AA6") (pinfunction "GND_AA6") (pintype "power_in"))
      (node (ref "IC35") (pin "AA9") (pinfunction "GND_AA9") (pintype "power_in"))
      (node (ref "IC35") (pin "AB10") (pinfunction "GND_AB10") (pintype "power_in"))
      (node (ref "IC35") (pin "AB12") (pinfunction "GND_AB12") (pintype "power_in"))
      (node (ref "IC35") (pin "AB14") (pinfunction "GND_AB14") (pintype "power_in"))
      (node (ref "IC35") (pin "AB23") (pinfunction "GND_AB23") (pintype "power_in"))
      (node (ref "IC35") (pin "AB3") (pinfunction "GND_AB3") (pintype "power_in"))
      (node (ref "IC35") (pin "AB8") (pinfunction "GND_AB8") (pintype "power_in"))
      (node (ref "IC35") (pin "AB9") (pinfunction "GND_AB9") (pintype "power_in"))
      (node (ref "IC35") (pin "AC15") (pinfunction "GND_AC15") (pintype "power_in"))
      (node (ref "IC35") (pin "AC20") (pinfunction "GND_AC20") (pintype "power_in"))
      (node (ref "IC35") (pin "AC7") (pinfunction "GND_AC7") (pintype "power_in"))
      (node (ref "IC35") (pin "AD11") (pinfunction "GND_AD11") (pintype "power_in"))
      (node (ref "IC35") (pin "AD13") (pinfunction "GND_AD13") (pintype "power_in"))
      (node (ref "IC35") (pin "AD16") (pinfunction "GND_AD16") (pintype "power_in"))
      (node (ref "IC35") (pin "AD6") (pinfunction "GND_AD6") (pintype "power_in"))
      (node (ref "IC35") (pin "AD9") (pinfunction "GND_AD9") (pintype "power_in"))
      (node (ref "IC35") (pin "AE15") (pinfunction "GND_AE15") (pintype "power_in"))
      (node (ref "IC35") (pin "AE24") (pinfunction "GND_AE24") (pintype "power_in"))
      (node (ref "IC35") (pin "AE4") (pinfunction "GND_AE4") (pintype "power_in"))
      (node (ref "IC35") (pin "AE6") (pinfunction "GND_AE6") (pintype "power_in"))
      (node (ref "IC35") (pin "AF1") (pinfunction "GND_AF1") (pintype "power_in"))
      (node (ref "IC35") (pin "AF10") (pinfunction "GND_AF10") (pintype "power_in"))
      (node (ref "IC35") (pin "AF12") (pinfunction "GND_AF12") (pintype "power_in"))
      (node (ref "IC35") (pin "AF14") (pinfunction "GND_AF14") (pintype "power_in"))
      (node (ref "IC35") (pin "AF16") (pinfunction "GND_AF16") (pintype "power_in"))
      (node (ref "IC35") (pin "AF21") (pinfunction "GND_AF21") (pintype "power_in"))
      (node (ref "IC35") (pin "AF6") (pinfunction "GND_AF6") (pintype "power_in"))
      (node (ref "IC35") (pin "AF8") (pinfunction "GND_AF8") (pintype "power_in"))
      (node (ref "IC35") (pin "B15") (pinfunction "GND_B15") (pintype "power_in"))
      (node (ref "IC35") (pin "B16") (pinfunction "GND_B16") (pintype "power_in"))
      (node (ref "IC35") (pin "B23") (pinfunction "GND_B23") (pintype "power_in"))
      (node (ref "IC35") (pin "B3") (pinfunction "GND_B3") (pintype "power_in"))
      (node (ref "IC35") (pin "B6") (pinfunction "GND_B6") (pintype "power_in"))
      (node (ref "IC35") (pin "C11") (pinfunction "GND_C11") (pintype "power_in"))
      (node (ref "IC35") (pin "C13") (pinfunction "GND_C13") (pintype "power_in"))
      (node (ref "IC35") (pin "C16") (pinfunction "GND_C16") (pintype "power_in"))
      (node (ref "IC35") (pin "C20") (pinfunction "GND_C20") (pintype "power_in"))
      (node (ref "IC35") (pin "C6") (pinfunction "GND_C6") (pintype "power_in"))
      (node (ref "IC35") (pin "C9") (pinfunction "GND_C9") (pintype "power_in"))
      (node (ref "IC35") (pin "D15") (pinfunction "GND_D15") (pintype "power_in"))
      (node (ref "IC35") (pin "D17") (pinfunction "GND_D17") (pintype "power_in"))
      (node (ref "IC35") (pin "D7") (pinfunction "GND_D7") (pintype "power_in"))
      (node (ref "IC35") (pin "E10") (pinfunction "GND_E10") (pintype "power_in"))
      (node (ref "IC35") (pin "E12") (pinfunction "GND_E12") (pintype "power_in"))
      (node (ref "IC35") (pin "E14") (pinfunction "GND_E14") (pintype "power_in"))
      (node (ref "IC35") (pin "E15") (pinfunction "GND_E15") (pintype "power_in"))
      (node (ref "IC35") (pin "E24") (pinfunction "GND_E24") (pintype "power_in"))
      (node (ref "IC35") (pin "E4") (pinfunction "GND_E4") (pintype "power_in"))
      (node (ref "IC35") (pin "E7") (pinfunction "GND_E7") (pintype "power_in"))
      (node (ref "IC35") (pin "E8") (pinfunction "GND_E8") (pintype "power_in"))
      (node (ref "IC35") (pin "E9") (pinfunction "GND_E9") (pintype "power_in"))
      (node (ref "IC35") (pin "F1") (pinfunction "GND_F1") (pintype "power_in"))
      (node (ref "IC35") (pin "F14") (pinfunction "GND_F14") (pintype "power_in"))
      (node (ref "IC35") (pin "F21") (pinfunction "GND_F21") (pintype "power_in"))
      (node (ref "IC35") (pin "F9") (pinfunction "GND_F9") (pintype "power_in"))
      (node (ref "IC35") (pin "G10") (pinfunction "GND_G10") (pintype "power_in"))
      (node (ref "IC35") (pin "G11") (pinfunction "GND_G11") (pintype "power_in"))
      (node (ref "IC35") (pin "G12") (pinfunction "GND_G12") (pintype "power_in"))
      (node (ref "IC35") (pin "G13") (pinfunction "GND_G13") (pintype "power_in"))
      (node (ref "IC35") (pin "G18") (pinfunction "GND_G18") (pintype "power_in"))
      (node (ref "IC35") (pin "H25") (pinfunction "GND_H25") (pintype "power_in"))
      (node (ref "IC35") (pin "H5") (pinfunction "GND_H5") (pintype "power_in"))
      (node (ref "IC35") (pin "J12") (pinfunction "GND_J12") (pintype "power_in"))
      (node (ref "IC35") (pin "J2") (pinfunction "GND_J2") (pintype "power_in"))
      (node (ref "IC35") (pin "J22") (pinfunction "GND_J22") (pintype "power_in"))
      (node (ref "IC35") (pin "K11") (pinfunction "GND_K11") (pintype "power_in"))
      (node (ref "IC35") (pin "K13") (pinfunction "GND_K13") (pintype "power_in"))
      (node (ref "IC35") (pin "K19") (pinfunction "GND_K19") (pintype "power_in"))
      (node (ref "IC35") (pin "K9") (pinfunction "GND_K9") (pintype "power_in"))
      (node (ref "IC35") (pin "L10") (pinfunction "GND_L10") (pintype "power_in"))
      (node (ref "IC35") (pin "L12") (pinfunction "GND_L12") (pintype "power_in"))
      (node (ref "IC35") (pin "L16") (pinfunction "GND_L16") (pintype "power_in"))
      (node (ref "IC35") (pin "L26") (pinfunction "GND_L26") (pintype "power_in"))
      (node (ref "IC35") (pin "L6") (pinfunction "GND_L6") (pintype "power_in"))
      (node (ref "IC35") (pin "M13") (pinfunction "GND_M13") (pintype "power_in"))
      (node (ref "IC35") (pin "M23") (pinfunction "GND_M23") (pintype "power_in"))
      (node (ref "IC35") (pin "M3") (pinfunction "GND_M3") (pintype "power_in"))
      (node (ref "IC35") (pin "M9") (pinfunction "GND_M9") (pintype "power_in"))
      (node (ref "IC35") (pin "N10") (pinfunction "GND_N10") (pintype "power_in"))
      (node (ref "IC35") (pin "N20") (pinfunction "GND_N20") (pintype "power_in"))
      (node (ref "IC35") (pin "P13") (pinfunction "GND_P13") (pintype "power_in"))
      (node (ref "IC35") (pin "P17") (pinfunction "GND_P17") (pintype "power_in"))
      (node (ref "IC35") (pin "P7") (pinfunction "GND_P7") (pintype "power_in"))
      (node (ref "IC35") (pin "P9") (pinfunction "GND_P9") (pintype "power_in"))
      (node (ref "IC35") (pin "R10") (pinfunction "GND_R10") (pintype "power_in"))
      (node (ref "IC35") (pin "R24") (pinfunction "GND_R24") (pintype "power_in"))
      (node (ref "IC35") (pin "R4") (pinfunction "GND_R4") (pintype "power_in"))
      (node (ref "IC35") (pin "T1") (pinfunction "GND_T1") (pintype "power_in"))
      (node (ref "IC35") (pin "T11") (pinfunction "GND_T11") (pintype "power_in"))
      (node (ref "IC35") (pin "T13") (pinfunction "GND_T13") (pintype "power_in"))
      (node (ref "IC35") (pin "T21") (pinfunction "GND_T21") (pintype "power_in"))
      (node (ref "IC35") (pin "T9") (pinfunction "GND_T9") (pintype "power_in"))
      (node (ref "IC35") (pin "U10") (pinfunction "GND_U10") (pintype "power_in"))
      (node (ref "IC35") (pin "U12") (pinfunction "GND_U12") (pintype "power_in"))
      (node (ref "IC35") (pin "U18") (pinfunction "GND_U18") (pintype "power_in"))
      (node (ref "IC35") (pin "U8") (pinfunction "GND_U8") (pintype "power_in"))
      (node (ref "IC35") (pin "V13") (pinfunction "GND_V13") (pintype "power_in"))
      (node (ref "IC35") (pin "V15") (pinfunction "GND_V15") (pintype "power_in"))
      (node (ref "IC35") (pin "V25") (pinfunction "GND_V25") (pintype "power_in"))
      (node (ref "IC35") (pin "V5") (pinfunction "GND_V5") (pintype "power_in"))
      (node (ref "IC35") (pin "W12") (pinfunction "GND_W12") (pintype "power_in"))
      (node (ref "IC35") (pin "W2") (pinfunction "GND_W2") (pintype "power_in"))
      (node (ref "IC35") (pin "W22") (pinfunction "GND_W22") (pintype "power_in"))
      (node (ref "IC35") (pin "Y10") (pinfunction "GND_Y10") (pintype "power_in"))
      (node (ref "IC35") (pin "Y11") (pinfunction "GND_Y11") (pintype "power_in"))
      (node (ref "IC35") (pin "Y12") (pinfunction "GND_Y12") (pintype "power_in"))
      (node (ref "IC35") (pin "Y13") (pinfunction "GND_Y13") (pintype "power_in"))
      (node (ref "IC35") (pin "Y19") (pinfunction "GND_Y19") (pintype "power_in"))
    )
    (net (code "5") (name "GND_ADC") (class "Default")
      (node (ref "C496") (pin "1") (pinfunction "1_1") (pintype "passive"))
      (node (ref "C497") (pin "2") (pinfunction "2_2") (pintype "passive"))
      (node (ref "FR103") (pin "2") (pinfunction "2_2") (pintype "passive"))
      (node (ref "IC35") (pin "M11") (pinfunction "GNDADC_0_M11") (pintype "power_in"))
    )
    (net (code "6") (name "Net-(BATTH1-+)") (class "Default")
      (node (ref "BATTH1") (pin "1") (pinfunction "+_1") (pintype "passive"))
      (node (ref "R192") (pin "1") (pinfunction "1_1") (pintype "passive"))
    )
    (net (code "7") (name "VCC1P0") (class "Default")
      (node (ref "C465") (pin "2") (pinfunction "2_2") (pintype "passive"))
      (node (ref "C466") (pin "2") (pinfunction "2_2") (pintype "passive"))
      (node (ref "C467") (pin "2") (pinfunction "2_2") (pintype "passive"))
      (node (ref "C468") (pin "1") (pinfunction "1_1") (pintype "passive"))
      (node (ref "C469") (pin "1") (pinfunction "1_1") (pintype "passive"))
      (node (ref "C470") (pin "1") (pinfunction "1_1") (pintype "passive"))
      (node (ref "C471") (pin "1") (pinfunction "1_1") (pintype "passive"))
      (node (ref "FR100") (pin "2") (pinfunction "2_2") (pintype "passive"))
      (node (ref "IC35") (pin "N13") (pinfunction "VCCBRAM_N13") (pintype "power_in"))
      (node (ref "IC35") (pin "R13") (pinfunction "VCCBRAM_R13") (pintype "power_in"))
      (node (ref "IC35") (pin "U13") (pinfunction "VCCBRAM_U13") (pintype "power_in"))
      (node (ref "IC35") (pin "W13") (pinfunction "VCCBRAM_W13") (pintype "power_in"))
    )
    (net (code "8") (name "VCC1P0_INT") (class "Default")
      (node (ref "C441") (pin "2") (pinfunction "2_2") (pintype "passive"))
      (node (ref "C442") (pin "2") (pinfunction "2_2") (pintype "passive"))
      (node (ref "C443") (pin "2") (pinfunction "2_2") (pintype "passive"))
      (node (ref "C444") (pin "2") (pinfunction "2_2") (pintype "passive"))
      (node (ref "C445") (pin "1") (pinfunction "1_1") (pintype "passive"))
      (node (ref "C446") (pin "1") (pinfunction "1_1") (pintype "passive"))
      (node (ref "C447") (pin "1") (pinfunction "1_1") (pintype "passive"))
      (node (ref "C448") (pin "1") (pinfunction "1_1") (pintype "passive"))
      (node (ref "C449") (pin "1") (pinfunction "1_1") (pintype "passive"))
      (node (ref "C450") (pin "1") (pinfunction "1_1") (pintype "passive"))
      (node (ref "C451") (pin "1") (pinfunction "1_1") (pintype "passive"))
      (node (ref "C452") (pin "1") (pinfunction "1_1") (pintype "passive"))
      (node (ref "C453") (pin "1") (pinfunction "1_1") (pintype "passive"))
      (node (ref "C454") (pin "1") (pinfunction "1_1") (pintype "passive"))
      (node (ref "C455") (pin "1") (pinfunction "1_1") (pintype "passive"))
      (node (ref "C456") (pin "1") (pinfunction "1_1") (pintype "passive"))
      (node (ref "C457") (pin "1") (pinfunction "1_1") (pintype "passive"))
      (node (ref "IC35") (pin "J11") (pinfunction "VCCINT_J11") (pintype "power_in"))
      (node (ref "IC35") (pin "J13") (pinfunction "VCCINT_J13") (pintype "power_in"))
      (node (ref "IC35") (pin "K10") (pinfunction "VCCINT_K10") (pintype "power_in"))
      (node (ref "IC35") (pin "K12") (pinfunction "VCCINT_K12") (pintype "power_in"))
      (node (ref "IC35") (pin "L11") (pinfunction "VCCINT_L11") (pintype "power_in"))
      (node (ref "IC35") (pin "L13") (pinfunction "VCCINT_L13") (pintype "power_in"))
      (node (ref "IC35") (pin "M10") (pinfunction "VCCINT_M10") (pintype "power_in"))
      (node (ref "IC35") (pin "P10") (pinfunction "VCCINT_P10") (pintype "power_in"))
      (node (ref "IC35") (pin "T10") (pinfunction "VCCINT_T10") (pintype "power_in"))
      (node (ref "IC35") (pin "T12") (pinfunction "VCCINT_T12") (pintype "power_in"))
      (node (ref "IC35") (pin "U11") (pinfunction "VCCINT_U11") (pintype "power_in"))
      (node (ref "IC35") (pin "V10") (pinfunction "VCCINT_V10") (pintype "power_in"))
      (node (ref "IC35") (pin "V12") (pinfunction "VCCINT_V12") (pintype "power_in"))
    )
    (net (code "9") (name "VCC1P2") (class "Default")
      (node (ref "FR101") (pin "2") (pinfunction "2_2") (pintype "passive"))
    )
    (net (code "10") (name "VCC1P8") (class "Default")
      (node (ref "C458") (pin "2") (pinfunction "2_2") (pintype "passive"))
      (node (ref "C459") (pin "2") (pinfunction "2_2") (pintype "passive"))
      (node (ref "C460") (pin "1") (pinfunction "1_1") (pintype "passive"))
      (node (ref "C461") (pin "1") (pinfunction "1_1") (pintype "passive"))
      (node (ref "C462") (pin "1") (pinfunction "1_1") (pintype "passive"))
      (node (ref "C463") (pin "1") (pinfunction "1_1") (pintype "passive"))
      (node (ref "C464") (pin "1") (pinfunction "1_1") (pintype "passive"))
      (node (ref "FR102") (pin "1") (pinfunction "1_1") (pintype "passive"))
      (node (ref "IC35") (pin "J9") (pinfunction "VCCAUX_J9") (pintype "power_in"))
      (node (ref "IC35") (pin "L9") (pinfunction "VCCAUX_L9") (pintype "power_in"))
      (node (ref "IC35") (pin "N9") (pinfunction "VCCAUX_N9") (pintype "power_in"))
      (node (ref "IC35") (pin "R9") (pinfunction "VCCAUX_R9") (pintype "power_in"))
      (node (ref "IC35") (pin "U9") (pinfunction "VCCAUX_U9") (pintype "power_in"))
      (node (ref "R191") (pin "1") (pinfunction "1_1") (pintype "passive"))
    )
    (net (code "11") (name "VCC1P8_FADC") (class "Default")
      (node (ref "C496") (pin "2") (pinfunction "2_2") (pintype "passive"))
      (node (ref "C497") (pin "1") (pinfunction "1_1") (pintype "passive"))
      (node (ref "FR102") (pin "2") (pinfunction "2_2") (pintype "passive"))
      (node (ref "IC35") (pin "M12") (pinfunction "VCCADC_0_M12") (pintype "power_in"))
    )
    (net (code "12") (name "VCC2P5") (class "Default")
      (node (ref "C377") (pin "2") (pinfunction "2_2") (pintype "passive"))
      (node (ref "C378") (pin "2") (pinfunction "2_2") (pintype "passive"))
      (node (ref "C379") (pin "1") (pinfunction "1_1") (pintype "passive"))
      (node (ref "C380") (pin "1") (pinfunction "1_1") (pintype "passive"))
      (node (ref "C381") (pin "1") (pinfunction "1_1") (pintype "passive"))
      (node (ref "C382") (pin "1") (pinfunction "1_1") (pintype "passive"))
      (node (ref "C383") (pin "1") (pinfunction "1_1") (pintype "passive"))
      (node (ref "C384") (pin "1") (pinfunction "1_1") (pintype "passive"))
      (node (ref "C385") (pin "2") (pinfunction "2_2") (pintype "passive"))
      (node (ref "C386") (pin "2") (pinfunction "2_2") (pintype "passive"))
      (node (ref "C387") (pin "1") (pinfunction "1_1") (pintype "passive"))
      (node (ref "C388") (pin "1") (pinfunction "1_1") (pintype "passive"))
      (node (ref "C389") (pin "1") (pinfunction "1_1") (pintype "passive"))
      (node (ref "C390") (pin "1") (pinfunction "1_1") (pintype "passive"))
      (node (ref "C391") (pin "1") (pinfunction "1_1") (pintype "passive"))
      (node (ref "C392") (pin "1") (pinfunction "1_1") (pintype "passive"))
      (node (ref "C401") (pin "2") (pinfunction "2_2") (pintype "passive"))
      (node (ref "C402") (pin "2") (pinfunction "2_2") (pintype "passive"))
      (node (ref "C403") (pin "1") (pinfunction "1_1") (pintype "passive"))
      (node (ref "C404") (pin "1") (pinfunction "1_1") (pintype "passive"))
      (node (ref "C405") (pin "1") (pinfunction "1_1") (pintype "passive"))
      (node (ref "C406") (pin "1") (pinfunction "1_1") (pintype "passive"))
      (node (ref "C407") (pin "1") (pinfunction "1_1") (pintype "passive"))
      (node (ref "C408") (pin "1") (pinfunction "1_1") (pintype "passive"))
      (node (ref "C417") (pin "2") (pinfunction "2_2") (pintype "passive"))
      (node (ref "C418") (pin "2") (pinfunction "2_2") (pintype "passive"))
      (node (ref "C419") (pin "1") (pinfunction "1_1") (pintype "passive"))
      (node (ref "C420") (pin "1") (pinfunction "1_1") (pintype "passive"))
      (node (ref "C421") (pin "1") (pinfunction "1_1") (pintype "passive"))
      (node (ref "C422") (pin "1") (pinfunction "1_1") (pintype "passive"))
      (node (ref "C423") (pin "1") (pinfunction "1_1") (pintype "passive"))
      (node (ref "C424") (pin "1") (pinfunction "1_1") (pintype "passive"))
      (node (ref "C425") (pin "2") (pinfunction "2_2") (pintype "passive"))
      (node (ref "C426") (pin "2") (pinfunction "2_2") (pintype "passive"))
      (node (ref "C427") (pin "1") (pinfunction "1_1") (pintype "passive"))
      (node (ref "C428") (pin "1") (pinfunction "1_1") (pintype "passive"))
      (node (ref "C429") (pin "1") (pinfunction "1_1") (pintype "passive"))
      (node (ref "C430") (pin "1") (pinfunction "1_1") (pintype "passive"))
      (node (ref "C431") (pin "1") (pinfunction "1_1") (pintype "passive"))
      (node (ref "C432") (pin "1") (pinfunction "1_1") (pintype "passive"))
      (node (ref "C433") (pin "2") (pinfunction "2_2") (pintype "passive"))
      (node (ref "C434") (pin "2") (pinfunction "2_2") (pintype "passive"))
      (node (ref "C435") (pin "1") (pinfunction "1_1") (pintype "passive"))
      (node (ref "C436") (pin "1") (pinfunction "1_1") (pintype "passive"))
      (node (ref "C437") (pin "1") (pinfunction "1_1") (pintype "passive"))
      (node (ref "C438") (pin "1") (pinfunction "1_1") (pintype "passive"))
      (node (ref "C439") (pin "1") (pinfunction "1_1") (pintype "passive"))
      (node (ref "C440") (pin "1") (pinfunction "1_1") (pintype "passive"))
      (node (ref "IC35") (pin "A1") (pinfunction "VCCO_35_A1") (pintype "power_in"))
      (node (ref "IC35") (pin "A21") (pinfunction "VCCO_16_A21") (pintype "power_in"))
      (node (ref "IC35") (pin "AA21") (pinfunction "VCCO_12_AA21") (pintype "power_in"))
      (node (ref "IC35") (pin "AB18") (pinfunction "VCCO_12_AB18") (pintype "power_in"))
      (node (ref "IC35") (pin "AC25") (pinfunction "VCCO_13_AC25") (pintype "power_in"))
      (node (ref "IC35") (pin "AD22") (pinfunction "VCCO_12_AD22") (pintype "power_in"))
      (node (ref "IC35") (pin "AE19") (pinfunction "VCCO_12_AE19") (pintype "power_in"))
      (node (ref "IC35") (pin "AF26") (pinfunction "VCCO_12_AF26") (pintype "power_in"))
      (node (ref "IC35") (pin "B18") (pinfunction "VCCO_16_B18") (pintype "power_in"))
      (node (ref "IC35") (pin "C25") (pinfunction "VCCO_16_C25") (pintype "power_in"))
      (node (ref "IC35") (pin "C5") (pinfunction "VCCO_35_C5") (pintype "power_in"))
      (node (ref "IC35") (pin "D2") (pinfunction "VCCO_35_D2") (pintype "power_in"))
      (node (ref "IC35") (pin "D22") (pinfunction "VCCO_16_D22") (pintype "power_in"))
      (node (ref "IC35") (pin "E19") (pinfunction "VCCO_16_E19") (pintype "power_in"))
      (node (ref "IC35") (pin "F16") (pinfunction "VCCO_16_F16") (pintype "power_in"))
      (node (ref "IC35") (pin "F26") (pinfunction "VCCO_15_F26") (pintype "power_in"))
      (node (ref "IC35") (pin "F6") (pinfunction "VCCO_35_F6") (pintype "power_in"))
      (node (ref "IC35") (pin "G23") (pinfunction "VCCO_15_G23") (pintype "power_in"))
      (node (ref "IC35") (pin "G3") (pinfunction "VCCO_35_G3") (pintype "power_in"))
      (node (ref "IC35") (pin "H20") (pinfunction "VCCO_15_H20") (pintype "power_in"))
      (node (ref "IC35") (pin "J17") (pinfunction "VCCO_15_J17") (pintype "power_in"))
      (node (ref "IC35") (pin "J7") (pinfunction "VCCO_35_J7") (pintype "power_in"))
      (node (ref "IC35") (pin "K14") (pinfunction "VCCO_15_K14") (pintype "power_in"))
      (node (ref "IC35") (pin "K4") (pinfunction "VCCO_34_K4") (pintype "power_in"))
      (node (ref "IC35") (pin "L1") (pinfunction "VCCO_34_L1") (pintype "power_in"))
      (node (ref "IC35") (pin "M18") (pinfunction "VCCO_15_M18") (pintype "power_in"))
      (node (ref "IC35") (pin "M8") (pinfunction "VCCO_34_M8") (pintype "power_in"))
      (node (ref "IC35") (pin "N5") (pinfunction "VCCO_34_N5") (pintype "power_in"))
      (node (ref "IC35") (pin "P2") (pinfunction "VCCO_34_P2") (pintype "power_in"))
      (node (ref "IC35") (pin "T16") (pinfunction "VCCO_13_T16") (pintype "power_in"))
      (node (ref "IC35") (pin "T26") (pinfunction "VCCO_13_T26") (pintype "power_in"))
      (node (ref "IC35") (pin "T6") (pinfunction "VCCO_34_T6") (pintype "power_in"))
      (node (ref "IC35") (pin "U23") (pinfunction "VCCO_13_U23") (pintype "power_in"))
      (node (ref "IC35") (pin "V20") (pinfunction "VCCO_13_V20") (pintype "power_in"))
      (node (ref "IC35") (pin "W17") (pinfunction "VCCO_12_W17") (pintype "power_in"))
      (node (ref "IC35") (pin "Y24") (pinfunction "VCCO_13_Y24") (pintype "power_in"))
    )
    (net (code "13") (name "VCC3P3") (class "Default")
      (node (ref "C373") (pin "2") (pinfunction "2_2") (pintype "passive"))
      (node (ref "C374") (pin "2") (pinfunction "2_2") (pintype "passive"))
      (node (ref "C375") (pin "1") (pinfunction "1_1") (pintype "passive"))
      (node (ref "C376") (pin "1") (pinfunction "1_1") (pintype "passive"))
      (node (ref "C409") (pin "2") (pinfunction "2_2") (pintype "passive"))
      (node (ref "C410") (pin "2") (pinfunction "2_2") (pintype "passive"))
      (node (ref "C411") (pin "1") (pinfunction "1_1") (pintype "passive"))
      (node (ref "C412") (pin "1") (pinfunction "1_1") (pintype "passive"))
      (node (ref "C413") (pin "1") (pinfunction "1_1") (pintype "passive"))
      (node (ref "C414") (pin "1") (pinfunction "1_1") (pintype "passive"))
      (node (ref "C415") (pin "1") (pinfunction "1_1") (pintype "passive"))
      (node (ref "C416") (pin "1") (pinfunction "1_1") (pintype "passive"))
      (node (ref "IC35") (pin "K24") (pinfunction "VCCO_14_K24") (pintype "power_in"))
      (node (ref "IC35") (pin "L21") (pinfunction "VCCO_14_L21") (pintype "power_in"))
      (node (ref "IC35") (pin "N15") (pinfunction "VCCO_14_N15") (pintype "power_in"))
      (node (ref "IC35") (pin "N25") (pinfunction "VCCO_14_N25") (pintype "power_in"))
      (node (ref "IC35") (pin "P22") (pinfunction "VCCO_14_P22") (pintype "power_in"))
      (node (ref "IC35") (pin "R19") (pinfunction "VCCO_14_R19") (pintype "power_in"))
      (node (ref "IC35") (pin "W11") (pinfunction "VCCO_0_W11") (pintype "power_in"))
      (node (ref "IC35") (pin "Y14") (pinfunction "VCCO_0_Y14") (pintype "power_in"))
    )
    (net (code "14") (name "VDIO_LMS_FPGA") (class "Default")
      (node (ref "C393") (pin "2") (pinfunction "2_2") (pintype "passive"))
      (node (ref "C394") (pin "2") (pinfunction "2_2") (pintype "passive"))
      (node (ref "C395") (pin "1") (pinfunction "1_1") (pintype "passive"))
      (node (ref "C396") (pin "1") (pinfunction "1_1") (pintype "passive"))
      (node (ref "C397") (pin "1") (pinfunction "1_1") (pintype "passive"))
      (node (ref "C398") (pin "1") (pinfunction "1_1") (pintype "passive"))
      (node (ref "C399") (pin "1") (pinfunction "1_1") (pintype "passive"))
      (node (ref "C400") (pin "1") (pinfunction "1_1") (pintype "passive"))
      (node (ref "IC35") (pin "AA1") (pinfunction "VCCO_33_AA1") (pintype "power_in"))
      (node (ref "IC35") (pin "AC5") (pinfunction "VCCO_33_AC5") (pintype "power_in"))
      (node (ref "IC35") (pin "AD2") (pinfunction "VCCO_33_AD2") (pintype "power_in"))
      (node (ref "IC35") (pin "U3") (pinfunction "VCCO_33_U3") (pintype "power_in"))
      (node (ref "IC35") (pin "W7") (pinfunction "VCCO_33_W7") (pintype "power_in"))
      (node (ref "IC35") (pin "Y4") (pinfunction "VCCO_33_Y4") (pintype "power_in"))
    )
    (net (code "15") (name "unconnected-(BATT1-PadNEGATIVE)") (class "Default")
      (node (ref "BATT1") (pin "NEGATIVE") (pintype "passive+no_connect"))
    )
    (net (code "16") (name "unconnected-(BATT1-PadPOSITIVE)") (class "Default")
      (node (ref "BATT1") (pin "POSITIVE") (pintype "passive+no_connect"))
    )
  )
)
